# bleumaus-nrf51822-mk-1_0_0.net
KiCad netlist of a schematic drawn in EAGLE
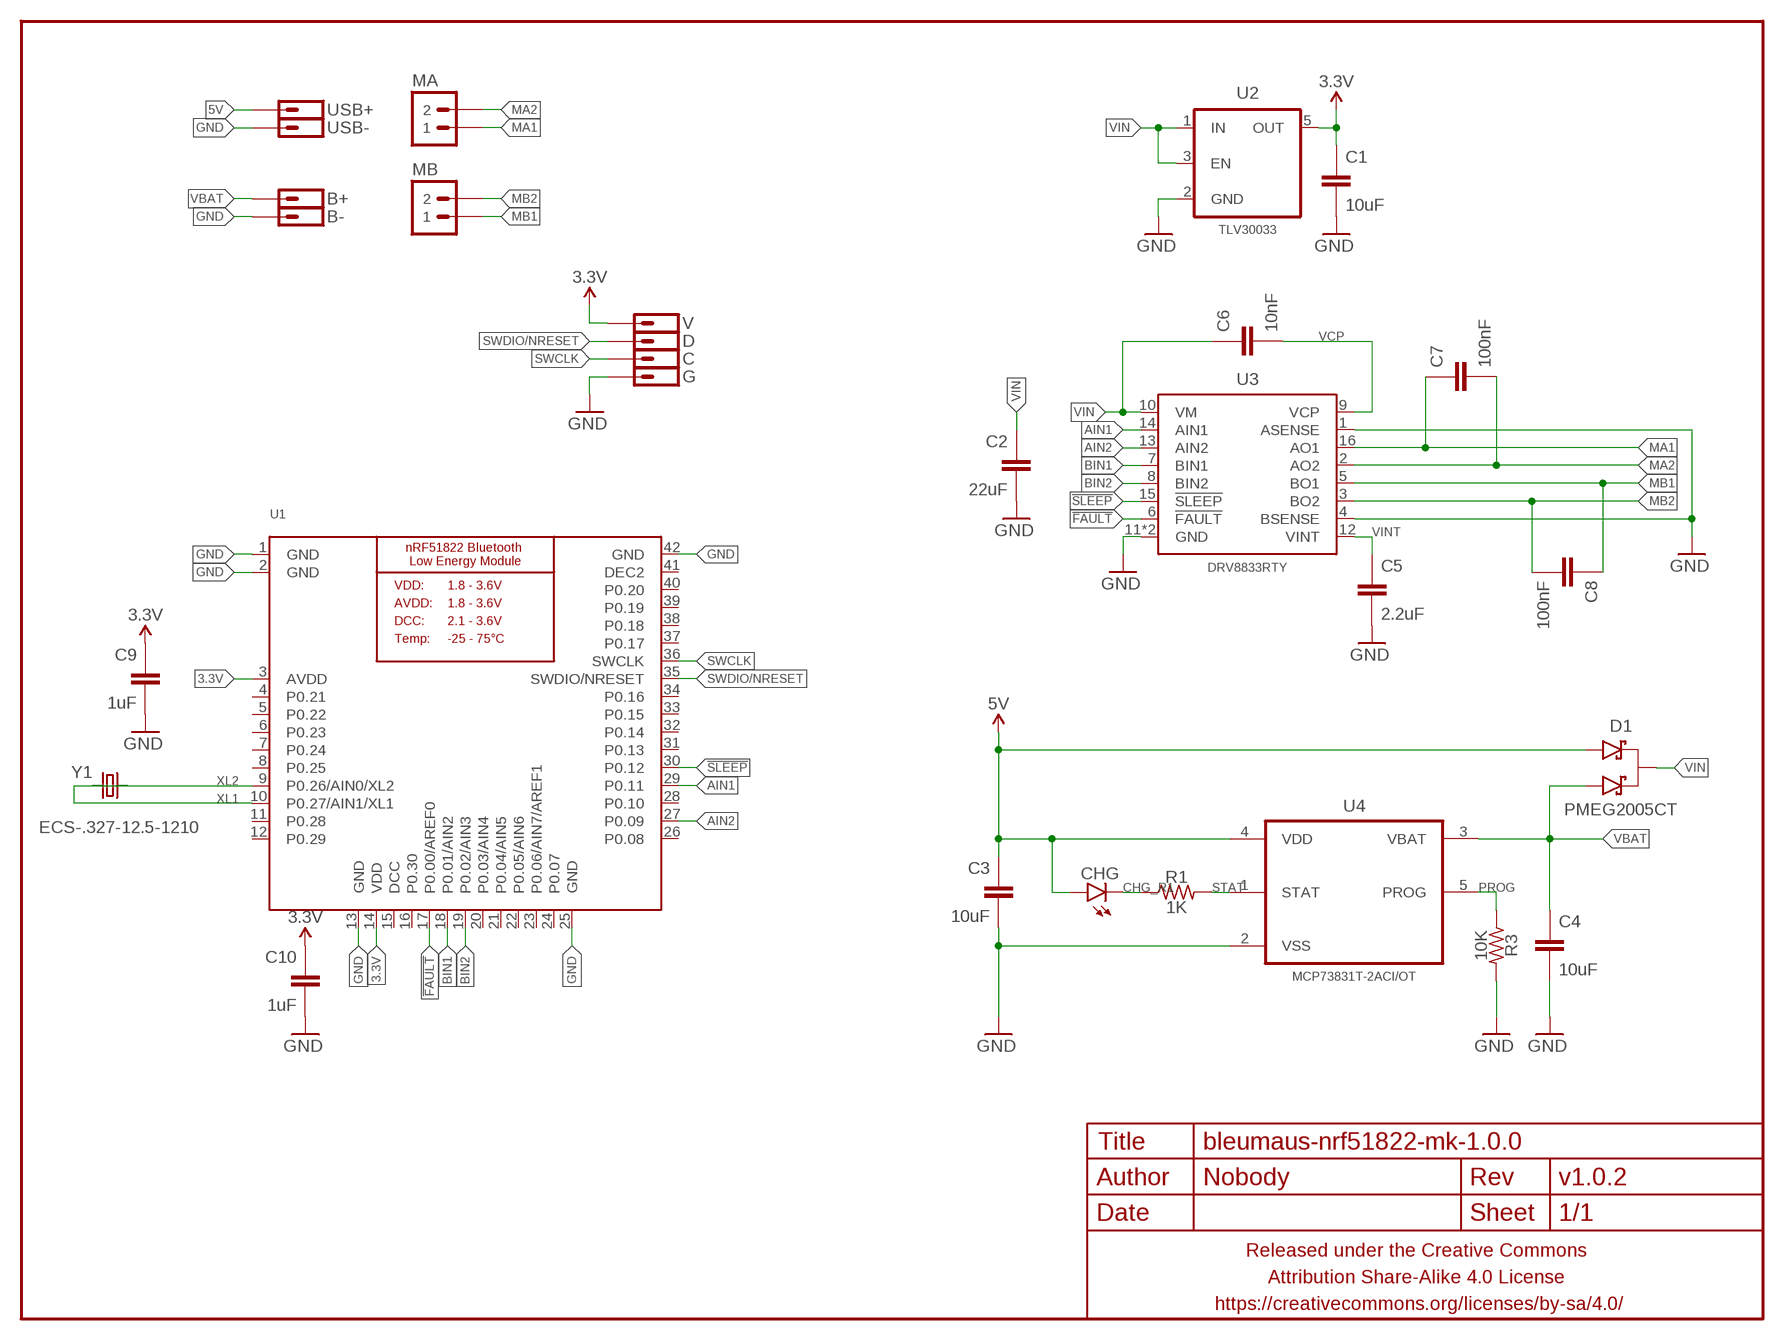
[diagram p0: schematic, sheet 1]

(export (version "E")
  (design (tool "Eeschema 10.0.6"))
  (components
    (comp (ref "B+")
      (value "M01SMD-1DIA")
      (footprint "eagle-import:1X01-SMD-1MM-DIA")
      (libsource (lib "eagle-import") (part "M01SMD-1DIA"))
    )
    (comp (ref "B-")
      (value "M01SMD-1DIA")
      (footprint "eagle-import:1X01-SMD-1MM-DIA")
      (libsource (lib "eagle-import") (part "M01SMD-1DIA"))
    )
    (comp (ref "C")
      (value "M01SMD-1DIA")
      (footprint "eagle-import:1X01-SMD-1MM-DIA")
      (libsource (lib "eagle-import") (part "M01SMD-1DIA"))
    )
    (comp (ref "C1")
      (value "10uF")
      (footprint "eagle-import:C0402")
      (libsource (lib "eagle-import") (part "CAPACITOR-CERAMICC0402"))
    )
    (comp (ref "C2")
      (value "22uF")
      (footprint "eagle-import:C1206")
      (libsource (lib "eagle-import") (part "CAPACITOR-CERAMICC1206"))
    )
    (comp (ref "C3")
      (value "10uF")
      (footprint "eagle-import:C0402")
      (libsource (lib "eagle-import") (part "CAPACITOR-CERAMICC0402"))
    )
    (comp (ref "C4")
      (value "10uF")
      (footprint "eagle-import:C0402")
      (libsource (lib "eagle-import") (part "CAPACITOR-CERAMICC0402"))
    )
    (comp (ref "C5")
      (value "2.2uF")
      (footprint "eagle-import:C0402")
      (libsource (lib "eagle-import") (part "CAPACITOR-CERAMICC0402"))
    )
    (comp (ref "C6")
      (value "10nF")
      (footprint "eagle-import:C0402")
      (libsource (lib "eagle-import") (part "CAPACITOR-CERAMICC0402"))
    )
    (comp (ref "C7")
      (value "100nF")
      (footprint "eagle-import:C0402")
      (libsource (lib "eagle-import") (part "CAPACITOR-CERAMICC0402"))
    )
    (comp (ref "C8")
      (value "100nF")
      (footprint "eagle-import:C0402")
      (libsource (lib "eagle-import") (part "CAPACITOR-CERAMICC0402"))
    )
    (comp (ref "C9")
      (value "1uF")
      (footprint "eagle-import:C0402")
      (libsource (lib "eagle-import") (part "CAPACITOR-CERAMICC0402"))
    )
    (comp (ref "C10")
      (value "1uF")
      (footprint "eagle-import:C0402")
      (libsource (lib "eagle-import") (part "CAPACITOR-CERAMICC0402"))
    )
    (comp (ref "CHG")
      (value "LED0603-TIGHT")
      (footprint "eagle-import:LED-0603-TIGHT")
      (libsource (lib "eagle-import") (part "LED0603-TIGHT"))
    )
    (comp (ref "D")
      (value "M01SMD-1DIA")
      (footprint "eagle-import:1X01-SMD-1MM-DIA")
      (libsource (lib "eagle-import") (part "M01SMD-1DIA"))
    )
    (comp (ref "D1")
      (value "PMEG2005CT")
      (footprint "eagle-import:SOT23")
      (libsource (lib "eagle-import") (part "DIODE-SCHOTTKY-DUALPMEG2005CT"))
    )
    (comp (ref "FRAME1")
      (value "FRAME-LETTERNO_PACKAGE")
      (footprint "eagle-import:DUMMY")
      (fields
        (field (name "DESIGNER") "Nobody")
        (field (name "VERSION") "v01")
        (field (name "VERSION_1") "v1.0.2")
      )
      (libsource (lib "eagle-import") (part "FRAME-LETTERNO_PACKAGE"))
    )
    (comp (ref "G")
      (value "M01SMD-1DIA")
      (footprint "eagle-import:1X01-SMD-1MM-DIA")
      (libsource (lib "eagle-import") (part "M01SMD-1DIA"))
    )
    (comp (ref "MA")
      (value "M02PTH-2MM")
      (footprint "eagle-import:1X02-2MM-PTH")
      (libsource (lib "eagle-import") (part "M02PTH-2MM"))
    )
    (comp (ref "MB")
      (value "M02PTH-2MM")
      (footprint "eagle-import:1X02-2MM-PTH")
      (libsource (lib "eagle-import") (part "M02PTH-2MM"))
    )
    (comp (ref "R1")
      (value "1K")
      (footprint "eagle-import:R0402")
      (libsource (lib "eagle-import") (part "RESISTORR0402"))
    )
    (comp (ref "R3")
      (value "10K")
      (footprint "eagle-import:R0402")
      (libsource (lib "eagle-import") (part "RESISTORR0402"))
    )
    (comp (ref "U1")
      (value "NRF51822_MODULE_MDBT40")
      (footprint "eagle-import:BLE_MODULE_RAYTAC_MDBT40")
      (libsource (lib "eagle-import") (part "NRF51822_MODULE_MDBT40"))
    )
    (comp (ref "U2")
      (value "TLV30033")
      (footprint "eagle-import:SC70-TIGHTER")
      (libsource (lib "eagle-import") (part "V_REG_ENTLV700XXDCK-TIGHTER"))
    )
    (comp (ref "U3")
      (value "DRV8833RTY")
      (footprint "eagle-import:PWQFN-16")
      (libsource (lib "eagle-import") (part "DRV8833RTY"))
    )
    (comp (ref "U4")
      (value "MCP73831T-2ACI/OT")
      (footprint "eagle-import:SOT95P280X145-5N")
      (libsource (lib "eagle-import") (part "MCP73831T-2ACI/OT"))
    )
    (comp (ref "USB+")
      (value "M01SMD-1DIA")
      (footprint "eagle-import:1X01-SMD-1MM-DIA")
      (libsource (lib "eagle-import") (part "M01SMD-1DIA"))
    )
    (comp (ref "USB-")
      (value "M01SMD-1DIA")
      (footprint "eagle-import:1X01-SMD-1MM-DIA")
      (libsource (lib "eagle-import") (part "M01SMD-1DIA"))
    )
    (comp (ref "V")
      (value "M01SMD-1DIA")
      (footprint "eagle-import:1X01-SMD-1MM-DIA")
      (libsource (lib "eagle-import") (part "M01SMD-1DIA"))
    )
    (comp (ref "Y1")
      (value "ECS-.327-12.5-1210")
      (footprint "eagle-import:CRYSTAL-1X1.2MM")
      (libsource (lib "eagle-import") (part "CRYSTAL1X1.2MM"))
    )
  )
  (nets
    (net (code "1") (name "/CHG_R1") (class "Default")
      (node (ref "CHG") (pin "C") (pinfunction "C_C") (pintype "passive"))
      (node (ref "R1") (pin "1") (pinfunction "1_1") (pintype "passive"))
    )
    (net (code "2") (name "/DCC") (class "Default")
      (node (ref "U1") (pin "15") (pinfunction "DCC_15") (pintype "power_in"))
    )
    (net (code "3") (name "/DEC2") (class "Default")
      (node (ref "U1") (pin "41") (pinfunction "DEC2_41") (pintype "power_in"))
    )
    (net (code "4") (name "/PROG") (class "Default")
      (node (ref "R3") (pin "1") (pinfunction "1_1") (pintype "passive"))
      (node (ref "U4") (pin "5") (pinfunction "PROG_5") (pintype "input"))
    )
    (net (code "5") (name "/STAT") (class "Default")
      (node (ref "R1") (pin "2") (pinfunction "2_2") (pintype "passive"))
      (node (ref "U4") (pin "1") (pinfunction "STAT_1") (pintype "output"))
    )
    (net (code "6") (name "/VCP") (class "Default")
      (node (ref "C6") (pin "2") (pinfunction "2_2") (pintype "passive"))
      (node (ref "U3") (pin "9") (pinfunction "VCP_9") (pintype "bidirectional"))
    )
    (net (code "7") (name "/VINT") (class "Default")
      (node (ref "C5") (pin "1") (pinfunction "1_1") (pintype "passive"))
      (node (ref "U3") (pin "12") (pinfunction "VINT_12") (pintype "bidirectional"))
    )
    (net (code "8") (name "/XL1") (class "Default")
      (node (ref "U1") (pin "10") (pinfunction "P0.27/AIN1/XL1_10") (pintype "bidirectional"))
      (node (ref "Y1") (pin "1") (pinfunction "1_1") (pintype "passive"))
    )
    (net (code "9") (name "/XL2") (class "Default")
      (node (ref "U1") (pin "9") (pinfunction "P0.26/AIN0/XL2_9") (pintype "bidirectional"))
      (node (ref "Y1") (pin "2") (pinfunction "2_2") (pintype "passive"))
    )
    (net (code "10") (name "/~{FAULT}") (class "Default")
      (node (ref "U1") (pin "17") (pinfunction "P0.00/AREF0_17") (pintype "bidirectional"))
      (node (ref "U3") (pin "6") (pinfunction "~{FAULT}_6") (pintype "output"))
    )
    (net (code "11") (name "/~{SLEEP}") (class "Default")
      (node (ref "U1") (pin "30") (pinfunction "P0.12_30") (pintype "bidirectional"))
      (node (ref "U3") (pin "15") (pinfunction "~{SLEEP}_15") (pintype "input"))
    )
    (net (code "12") (name "3.3V") (class "Default")
      (node (ref "C1") (pin "1") (pinfunction "1_1") (pintype "passive"))
      (node (ref "C10") (pin "1") (pinfunction "1_1") (pintype "passive"))
      (node (ref "C9") (pin "1") (pinfunction "1_1") (pintype "passive"))
      (node (ref "U1") (pin "14") (pinfunction "VDD_14") (pintype "power_in"))
      (node (ref "U1") (pin "3") (pinfunction "AVDD_3") (pintype "power_in"))
      (node (ref "U2") (pin "5") (pinfunction "OUT_5") (pintype "passive"))
      (node (ref "V") (pin "P$1") (pinfunction "1_P$1") (pintype "passive"))
    )
    (net (code "13") (name "5V") (class "Default")
      (node (ref "C3") (pin "1") (pinfunction "1_1") (pintype "passive"))
      (node (ref "CHG") (pin "A") (pinfunction "A_A") (pintype "passive"))
      (node (ref "D1") (pin "1") (pinfunction "A1_1") (pintype "passive"))
      (node (ref "U4") (pin "4") (pinfunction "VDD_4") (pintype "power_in"))
      (node (ref "USB+") (pin "P$1") (pinfunction "1_P$1") (pintype "passive"))
    )
    (net (code "14") (name "AIN1") (class "Default")
      (node (ref "U1") (pin "29") (pinfunction "P0.11_29") (pintype "bidirectional"))
      (node (ref "U3") (pin "14") (pinfunction "AIN1_14") (pintype "input"))
    )
    (net (code "15") (name "AIN2") (class "Default")
      (node (ref "U1") (pin "27") (pinfunction "P0.09_27") (pintype "bidirectional"))
      (node (ref "U3") (pin "13") (pinfunction "AIN2_13") (pintype "input"))
    )
    (net (code "16") (name "BIN1") (class "Default")
      (node (ref "U1") (pin "18") (pinfunction "P0.01/AIN2_18") (pintype "bidirectional"))
      (node (ref "U3") (pin "7") (pinfunction "BIN1_7") (pintype "input"))
    )
    (net (code "17") (name "BIN2") (class "Default")
      (node (ref "U1") (pin "19") (pinfunction "P0.02/AIN3_19") (pintype "bidirectional"))
      (node (ref "U3") (pin "8") (pinfunction "BIN2_8") (pintype "input"))
    )
    (net (code "18") (name "GND") (class "Default")
      (node (ref "B-") (pin "P$1") (pinfunction "1_P$1") (pintype "passive"))
      (node (ref "C1") (pin "2") (pinfunction "2_2") (pintype "passive"))
      (node (ref "C10") (pin "2") (pinfunction "2_2") (pintype "passive"))
      (node (ref "C2") (pin "2") (pinfunction "2_2") (pintype "passive"))
      (node (ref "C3") (pin "2") (pinfunction "2_2") (pintype "passive"))
      (node (ref "C4") (pin "2") (pinfunction "2_2") (pintype "passive"))
      (node (ref "C5") (pin "2") (pinfunction "2_2") (pintype "passive"))
      (node (ref "C9") (pin "2") (pinfunction "2_2") (pintype "passive"))
      (node (ref "G") (pin "P$1") (pinfunction "1_P$1") (pintype "passive"))
      (node (ref "R3") (pin "2") (pinfunction "2_2") (pintype "passive"))
      (node (ref "U1") (pin "1") (pinfunction "GND_1") (pintype "power_in"))
      (node (ref "U1") (pin "13") (pinfunction "GND_13") (pintype "power_in"))
      (node (ref "U1") (pin "2") (pinfunction "GND_2") (pintype "power_in"))
      (node (ref "U1") (pin "25") (pinfunction "GND_25") (pintype "power_in"))
      (node (ref "U1") (pin "42") (pinfunction "GND_42") (pintype "power_in"))
      (node (ref "U2") (pin "2") (pinfunction "GND_2") (pintype "input"))
      (node (ref "U3") (pin "1") (pinfunction "ASENSE_1") (pintype "bidirectional"))
      (node (ref "U3") (pin "11") (pinfunction "GND_11") (pintype "bidirectional"))
      (node (ref "U3") (pin "17") (pinfunction "GND_17") (pintype "bidirectional"))
      (node (ref "U3") (pin "4") (pinfunction "BSENSE_4") (pintype "bidirectional"))
      (node (ref "U4") (pin "2") (pinfunction "VSS_2") (pintype "power_in"))
      (node (ref "USB-") (pin "P$1") (pinfunction "1_P$1") (pintype "passive"))
    )
    (net (code "19") (name "MA1") (class "Default")
      (node (ref "C7") (pin "1") (pinfunction "1_1") (pintype "passive"))
      (node (ref "MA") (pin "P$1") (pinfunction "1_P$1") (pintype "passive"))
      (node (ref "U3") (pin "16") (pinfunction "AO1_16") (pintype "bidirectional"))
    )
    (net (code "20") (name "MA2") (class "Default")
      (node (ref "C7") (pin "2") (pinfunction "2_2") (pintype "passive"))
      (node (ref "MA") (pin "P$2") (pinfunction "2_P$2") (pintype "passive"))
      (node (ref "U3") (pin "2") (pinfunction "AO2_2") (pintype "bidirectional"))
    )
    (net (code "21") (name "MB1") (class "Default")
      (node (ref "C8") (pin "1") (pinfunction "1_1") (pintype "passive"))
      (node (ref "MB") (pin "P$1") (pinfunction "1_P$1") (pintype "passive"))
      (node (ref "U3") (pin "5") (pinfunction "BO1_5") (pintype "bidirectional"))
    )
    (net (code "22") (name "MB2") (class "Default")
      (node (ref "C8") (pin "2") (pinfunction "2_2") (pintype "passive"))
      (node (ref "MB") (pin "P$2") (pinfunction "2_P$2") (pintype "passive"))
      (node (ref "U3") (pin "3") (pinfunction "BO2_3") (pintype "bidirectional"))
    )
    (net (code "23") (name "SWCLK") (class "Default")
      (node (ref "C") (pin "P$1") (pinfunction "1_P$1") (pintype "passive"))
      (node (ref "U1") (pin "36") (pinfunction "SWCLK_36") (pintype "bidirectional"))
    )
    (net (code "24") (name "SWDIO{slash}NRESET") (class "Default")
      (node (ref "D") (pin "P$1") (pinfunction "1_P$1") (pintype "passive"))
      (node (ref "U1") (pin "35") (pinfunction "SWDIO/NRESET_35") (pintype "bidirectional"))
    )
    (net (code "25") (name "VBAT") (class "Default")
      (node (ref "B+") (pin "P$1") (pinfunction "1_P$1") (pintype "passive"))
      (node (ref "C4") (pin "1") (pinfunction "1_1") (pintype "passive"))
      (node (ref "D1") (pin "2") (pinfunction "A2_2") (pintype "passive"))
      (node (ref "U4") (pin "3") (pinfunction "VBAT_3") (pintype "output"))
    )
    (net (code "26") (name "VIN") (class "Default")
      (node (ref "C2") (pin "1") (pinfunction "1_1") (pintype "passive"))
      (node (ref "C6") (pin "1") (pinfunction "1_1") (pintype "passive"))
      (node (ref "D1") (pin "3") (pinfunction "K_3") (pintype "passive"))
      (node (ref "U2") (pin "1") (pinfunction "IN_1") (pintype "input"))
      (node (ref "U2") (pin "3") (pinfunction "EN_3") (pintype "input"))
      (node (ref "U3") (pin "10") (pinfunction "VM_10") (pintype "bidirectional"))
    )
    (net (code "27") (name "unconnected-(U1-P0.03{slash}AIN4-Pad20)") (class "Default")
      (node (ref "U1") (pin "20") (pinfunction "P0.03/AIN4_20") (pintype "bidirectional"))
    )
    (net (code "28") (name "unconnected-(U1-P0.04{slash}AIN5-Pad21)") (class "Default")
      (node (ref "U1") (pin "21") (pinfunction "P0.04/AIN5_21") (pintype "bidirectional"))
    )
    (net (code "29") (name "unconnected-(U1-P0.05{slash}AIN6-Pad22)") (class "Default")
      (node (ref "U1") (pin "22") (pinfunction "P0.05/AIN6_22") (pintype "bidirectional"))
    )
    (net (code "30") (name "unconnected-(U1-P0.06{slash}AIN7{slash}AREF1-Pad23)") (class "Default")
      (node (ref "U1") (pin "23") (pinfunction "P0.06/AIN7/AREF1_23") (pintype "bidirectional"))
    )
    (net (code "31") (name "unconnected-(U1-P0.07-Pad24)") (class "Default")
      (node (ref "U1") (pin "24") (pinfunction "P0.07_24") (pintype "bidirectional"))
    )
    (net (code "32") (name "unconnected-(U1-P0.08-Pad26)") (class "Default")
      (node (ref "U1") (pin "26") (pinfunction "P0.08_26") (pintype "bidirectional"))
    )
    (net (code "33") (name "unconnected-(U1-P0.10-Pad28)") (class "Default")
      (node (ref "U1") (pin "28") (pinfunction "P0.10_28") (pintype "bidirectional"))
    )
    (net (code "34") (name "unconnected-(U1-P0.13-Pad31)") (class "Default")
      (node (ref "U1") (pin "31") (pinfunction "P0.13_31") (pintype "bidirectional"))
    )
    (net (code "35") (name "unconnected-(U1-P0.14-Pad32)") (class "Default")
      (node (ref "U1") (pin "32") (pinfunction "P0.14_32") (pintype "bidirectional"))
    )
    (net (code "36") (name "unconnected-(U1-P0.15-Pad33)") (class "Default")
      (node (ref "U1") (pin "33") (pinfunction "P0.15_33") (pintype "bidirectional"))
    )
    (net (code "37") (name "unconnected-(U1-P0.16-Pad34)") (class "Default")
      (node (ref "U1") (pin "34") (pinfunction "P0.16_34") (pintype "bidirectional"))
    )
    (net (code "38") (name "unconnected-(U1-P0.17-Pad37)") (class "Default")
      (node (ref "U1") (pin "37") (pinfunction "P0.17_37") (pintype "bidirectional"))
    )
    (net (code "39") (name "unconnected-(U1-P0.18-Pad38)") (class "Default")
      (node (ref "U1") (pin "38") (pinfunction "P0.18_38") (pintype "bidirectional"))
    )
    (net (code "40") (name "unconnected-(U1-P0.19-Pad39)") (class "Default")
      (node (ref "U1") (pin "39") (pinfunction "P0.19_39") (pintype "bidirectional"))
    )
    (net (code "41") (name "unconnected-(U1-P0.20-Pad40)") (class "Default")
      (node (ref "U1") (pin "40") (pinfunction "P0.20_40") (pintype "bidirectional"))
    )
    (net (code "42") (name "unconnected-(U1-P0.21-Pad4)") (class "Default")
      (node (ref "U1") (pin "4") (pinfunction "P0.21_4") (pintype "bidirectional"))
    )
    (net (code "43") (name "unconnected-(U1-P0.22-Pad5)") (class "Default")
      (node (ref "U1") (pin "5") (pinfunction "P0.22_5") (pintype "bidirectional"))
    )
    (net (code "44") (name "unconnected-(U1-P0.23-Pad6)") (class "Default")
      (node (ref "U1") (pin "6") (pinfunction "P0.23_6") (pintype "bidirectional"))
    )
    (net (code "45") (name "unconnected-(U1-P0.24-Pad7)") (class "Default")
      (node (ref "U1") (pin "7") (pinfunction "P0.24_7") (pintype "bidirectional"))
    )
    (net (code "46") (name "unconnected-(U1-P0.25-Pad8)") (class "Default")
      (node (ref "U1") (pin "8") (pinfunction "P0.25_8") (pintype "bidirectional"))
    )
    (net (code "47") (name "unconnected-(U1-P0.28-Pad11)") (class "Default")
      (node (ref "U1") (pin "11") (pinfunction "P0.28_11") (pintype "bidirectional"))
    )
    (net (code "48") (name "unconnected-(U1-P0.29-Pad12)") (class "Default")
      (node (ref "U1") (pin "12") (pinfunction "P0.29_12") (pintype "bidirectional"))
    )
    (net (code "49") (name "unconnected-(U1-P0.30-Pad16)") (class "Default")
      (node (ref "U1") (pin "16") (pinfunction "P0.30_16") (pintype "bidirectional"))
    )
  )
)
